# VRS.net
KiCad netlist of a schematic drawn in Altium Designer
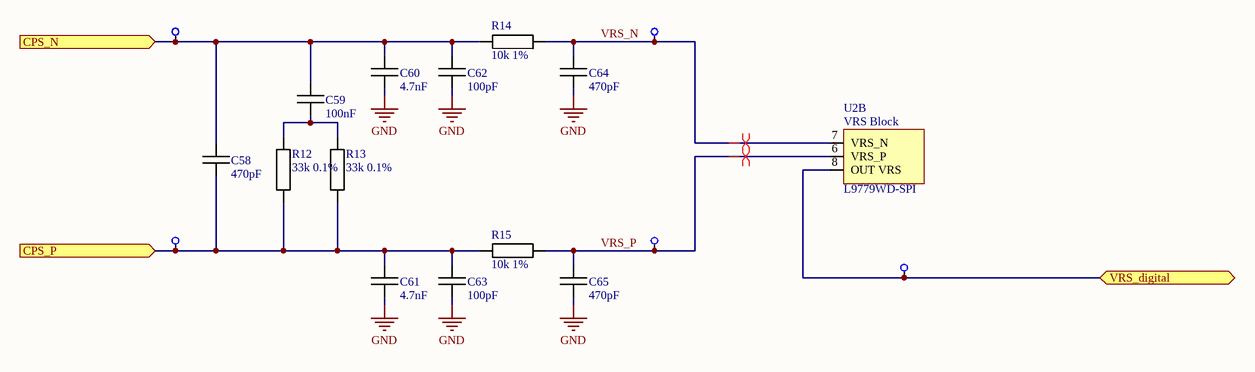
[diagram p0: VRS.SchDoc]

(export (version "E")
  (design (tool "Eeschema 10.0.6"))
  (components
    (comp (ref "C58")
      (value "470pF")
      (footprint "SMD 0603")
      (description "CC0603KRX7R9BB471")
      (libsource (lib "Maks_lib") (part "Capasitor"))
    )
    (comp (ref "C59")
      (value "100nF")
      (footprint "SMD 0603")
      (description "CC0603KRX7R9BB104")
      (libsource (lib "Maks_lib") (part "Capasitor"))
    )
    (comp (ref "C60")
      (value "4.7nF")
      (footprint "SMD 0603")
      (description "CC0603KRX7R9BB472")
      (libsource (lib "Maks_lib") (part "Capasitor"))
    )
    (comp (ref "C61")
      (value "4.7nF")
      (footprint "SMD 0603")
      (description "CC0603KRX7R9BB472")
      (libsource (lib "Maks_lib") (part "Capasitor"))
    )
    (comp (ref "C62")
      (value "100pF")
      (footprint "SMD 0603")
      (description "CC0603KRX7R9BB101")
      (libsource (lib "Maks_lib") (part "Capasitor"))
    )
    (comp (ref "C63")
      (value "100pF")
      (footprint "SMD 0603")
      (description "CC0603KRX7R9BB101")
      (libsource (lib "Maks_lib") (part "Capasitor"))
    )
    (comp (ref "C64")
      (value "470pF")
      (footprint "SMD 0603")
      (description "CC0603KRX7R9BB471")
      (libsource (lib "Maks_lib") (part "Capasitor"))
    )
    (comp (ref "C65")
      (value "470pF")
      (footprint "SMD 0603")
      (description "CC0603KRX7R9BB471")
      (libsource (lib "Maks_lib") (part "Capasitor"))
    )
    (comp (ref "R12")
      (value "33k 0.1%")
      (footprint "SMD 0603")
      (description "RT0603BRD0733KL")
      (libsource (lib "Maks_lib") (part "Resistor"))
    )
    (comp (ref "R13")
      (value "33k 0.1%")
      (footprint "SMD 0603")
      (description "RT0603BRD0733KL")
      (libsource (lib "Maks_lib") (part "Resistor"))
    )
    (comp (ref "R14")
      (value "10k 1%")
      (footprint "SMD 0603")
      (description "RT0603FRE0710KL")
      (libsource (lib "Maks_lib") (part "Resistor"))
    )
    (comp (ref "R15")
      (value "10k 1%")
      (footprint "SMD 0603")
      (description "RT0603FRE0710KL")
      (libsource (lib "Maks_lib") (part "Resistor"))
    )
    (comp (ref "TP38")
      (value "TestPoint")
      (footprint "TESTPOINT")
      (description "testPoint")
      (libsource (lib "Maks_lib") (part "TestPoint"))
    )
    (comp (ref "TP39")
      (value "TestPoint")
      (footprint "TESTPOINT")
      (description "testPoint")
      (libsource (lib "Maks_lib") (part "TestPoint"))
    )
    (comp (ref "TP40")
      (value "TestPoint")
      (footprint "TESTPOINT")
      (description "testPoint")
      (libsource (lib "Maks_lib") (part "TestPoint"))
    )
    (comp (ref "TP41")
      (value "TestPoint")
      (footprint "TESTPOINT")
      (description "testPoint")
      (libsource (lib "Maks_lib") (part "TestPoint"))
    )
    (comp (ref "TP42")
      (value "TestPoint")
      (footprint "TESTPOINT")
      (description "testPoint")
      (libsource (lib "Maks_lib") (part "TestPoint"))
    )
    (comp (ref "U2")
      (value "L9779WD-SPI")
      (footprint "HiQUAD-64")
      (description "Multifunction IC for engine management system")
      (libsource (lib "Maks_lib") (part "L9779WD-SPI"))
    )
  )
  (nets
    (net (code "1") (name "/CPS_N") (class "Default")
      (node (ref "C58") (pin "2") (pinfunction "2_2") (pintype "passive"))
      (node (ref "C59") (pin "1") (pinfunction "1_1") (pintype "passive"))
      (node (ref "C60") (pin "2") (pinfunction "2_2") (pintype "passive"))
      (node (ref "C62") (pin "2") (pinfunction "2_2") (pintype "passive"))
      (node (ref "R14") (pin "1") (pinfunction "1_1") (pintype "passive"))
      (node (ref "TP38") (pin "0") (pinfunction "0_0") (pintype "passive"))
    )
    (net (code "2") (name "/CPS_P") (class "Default")
      (node (ref "C58") (pin "1") (pinfunction "1_1") (pintype "passive"))
      (node (ref "C61") (pin "2") (pinfunction "2_2") (pintype "passive"))
      (node (ref "C63") (pin "2") (pinfunction "2_2") (pintype "passive"))
      (node (ref "R12") (pin "2") (pinfunction "2_2") (pintype "passive"))
      (node (ref "R13") (pin "2") (pinfunction "2_2") (pintype "passive"))
      (node (ref "R15") (pin "1") (pinfunction "1_1") (pintype "passive"))
      (node (ref "TP39") (pin "0") (pinfunction "0_0") (pintype "passive"))
    )
    (net (code "3") (name "/VRS_N") (class "Default")
      (node (ref "C64") (pin "2") (pinfunction "2_2") (pintype "passive"))
      (node (ref "R14") (pin "2") (pinfunction "2_2") (pintype "passive"))
      (node (ref "TP40") (pin "0") (pinfunction "0_0") (pintype "passive"))
      (node (ref "U2") (pin "7") (pinfunction "VRS_N_7") (pintype "passive"))
    )
    (net (code "4") (name "/VRS_P") (class "Default")
      (node (ref "C65") (pin "2") (pinfunction "2_2") (pintype "passive"))
      (node (ref "R15") (pin "2") (pinfunction "2_2") (pintype "passive"))
      (node (ref "TP41") (pin "0") (pinfunction "0_0") (pintype "passive"))
      (node (ref "U2") (pin "6") (pinfunction "VRS_P_6") (pintype "passive"))
    )
    (net (code "5") (name "/VRS_digital") (class "Default")
      (node (ref "TP42") (pin "0") (pinfunction "0_0") (pintype "passive"))
      (node (ref "U2") (pin "8") (pinfunction "OUT_VRS_8") (pintype "open_collector"))
    )
    (net (code "6") (name "GND") (class "Default")
      (node (ref "C60") (pin "1") (pinfunction "1_1") (pintype "passive"))
      (node (ref "C61") (pin "1") (pinfunction "1_1") (pintype "passive"))
      (node (ref "C62") (pin "1") (pinfunction "1_1") (pintype "passive"))
      (node (ref "C63") (pin "1") (pinfunction "1_1") (pintype "passive"))
      (node (ref "C64") (pin "1") (pinfunction "1_1") (pintype "passive"))
      (node (ref "C65") (pin "1") (pinfunction "1_1") (pintype "passive"))
    )
    (net (code "7") (name "Net-(C59-Pad2)") (class "Default")
      (node (ref "C59") (pin "2") (pinfunction "2_2") (pintype "passive"))
      (node (ref "R12") (pin "1") (pinfunction "1_1") (pintype "passive"))
      (node (ref "R13") (pin "1") (pinfunction "1_1") (pintype "passive"))
    )
  )
)
